# USB_IMU_Board.net
KiCad netlist of a schematic drawn in EAGLE
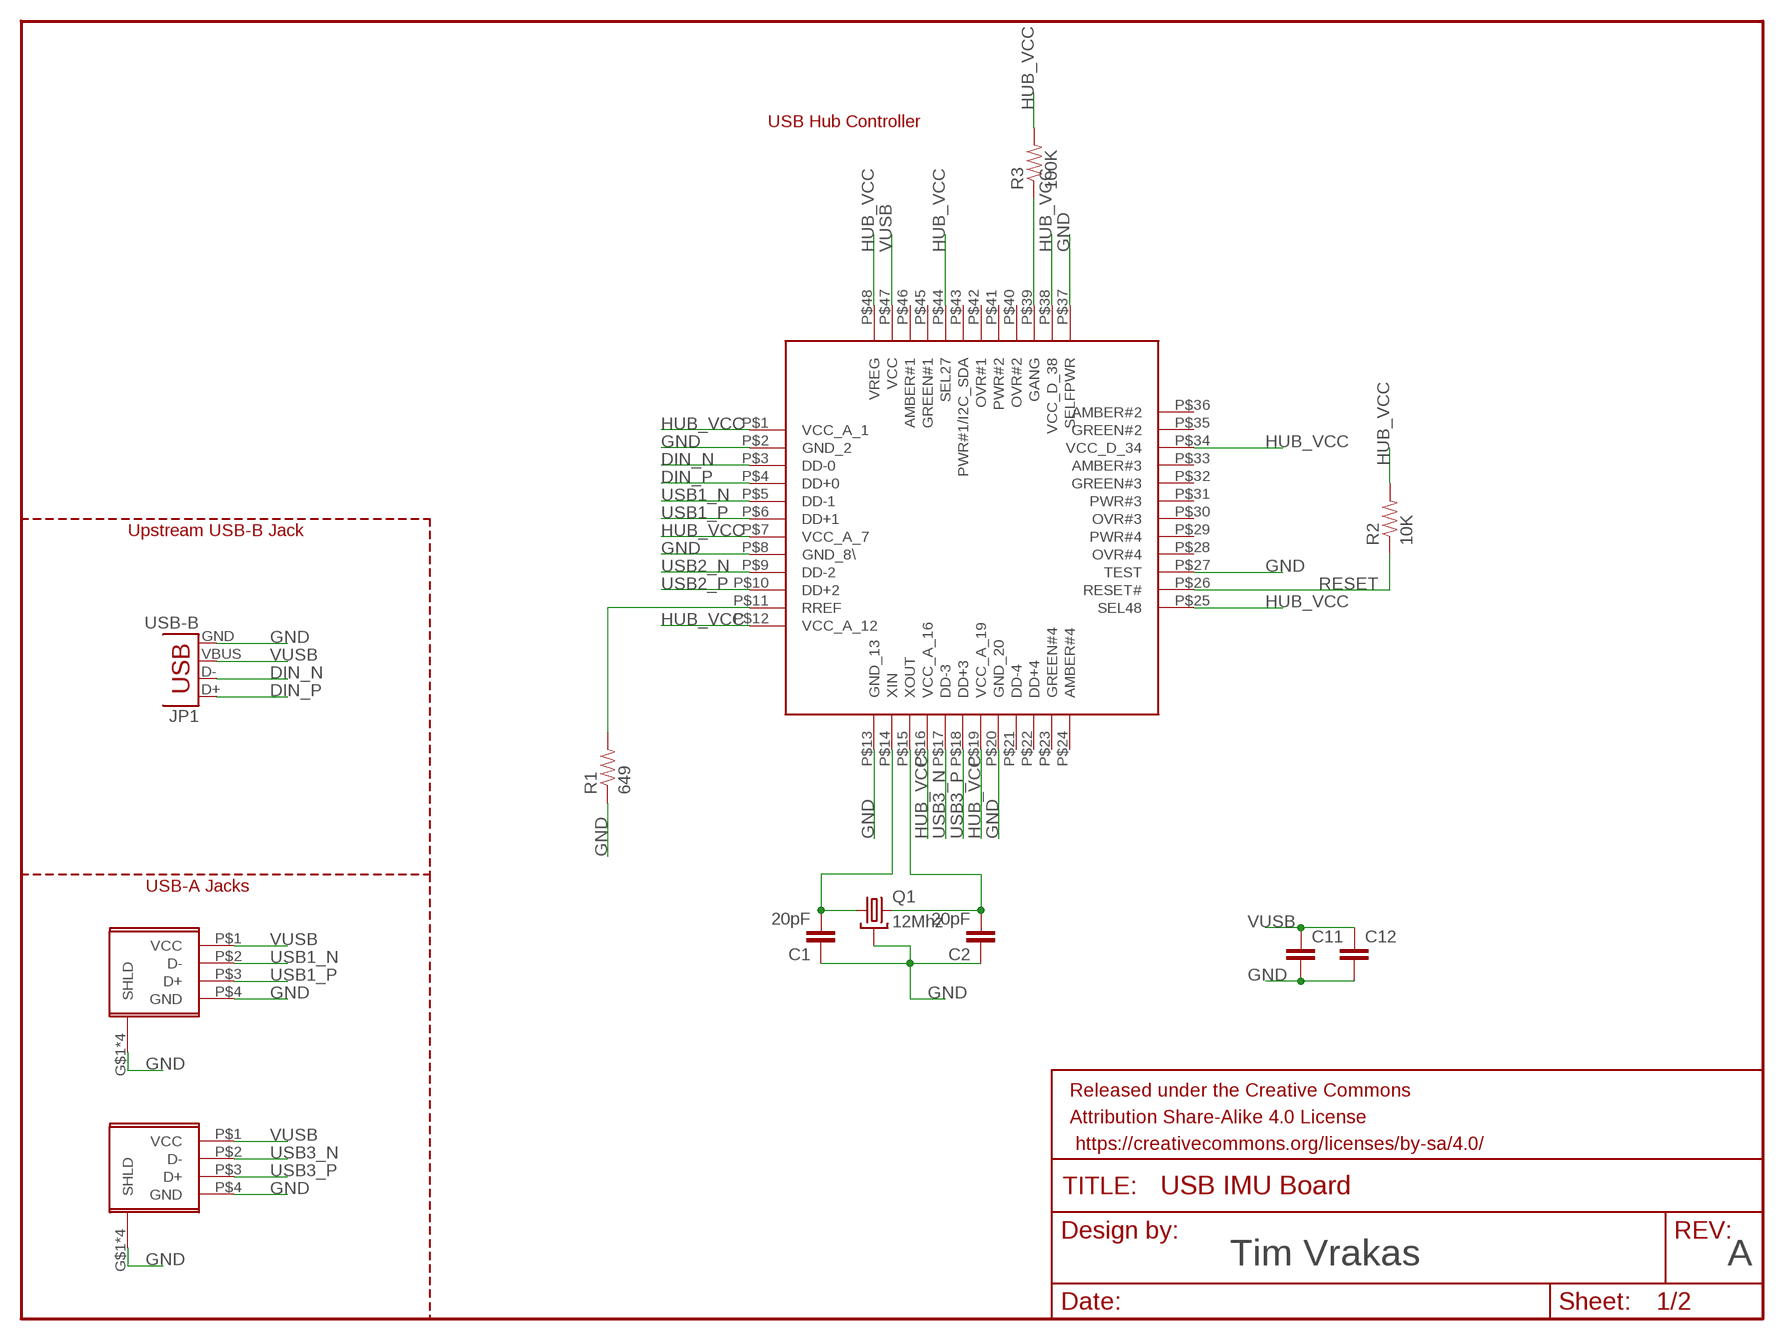
[diagram p0: schematic, sheet 1]
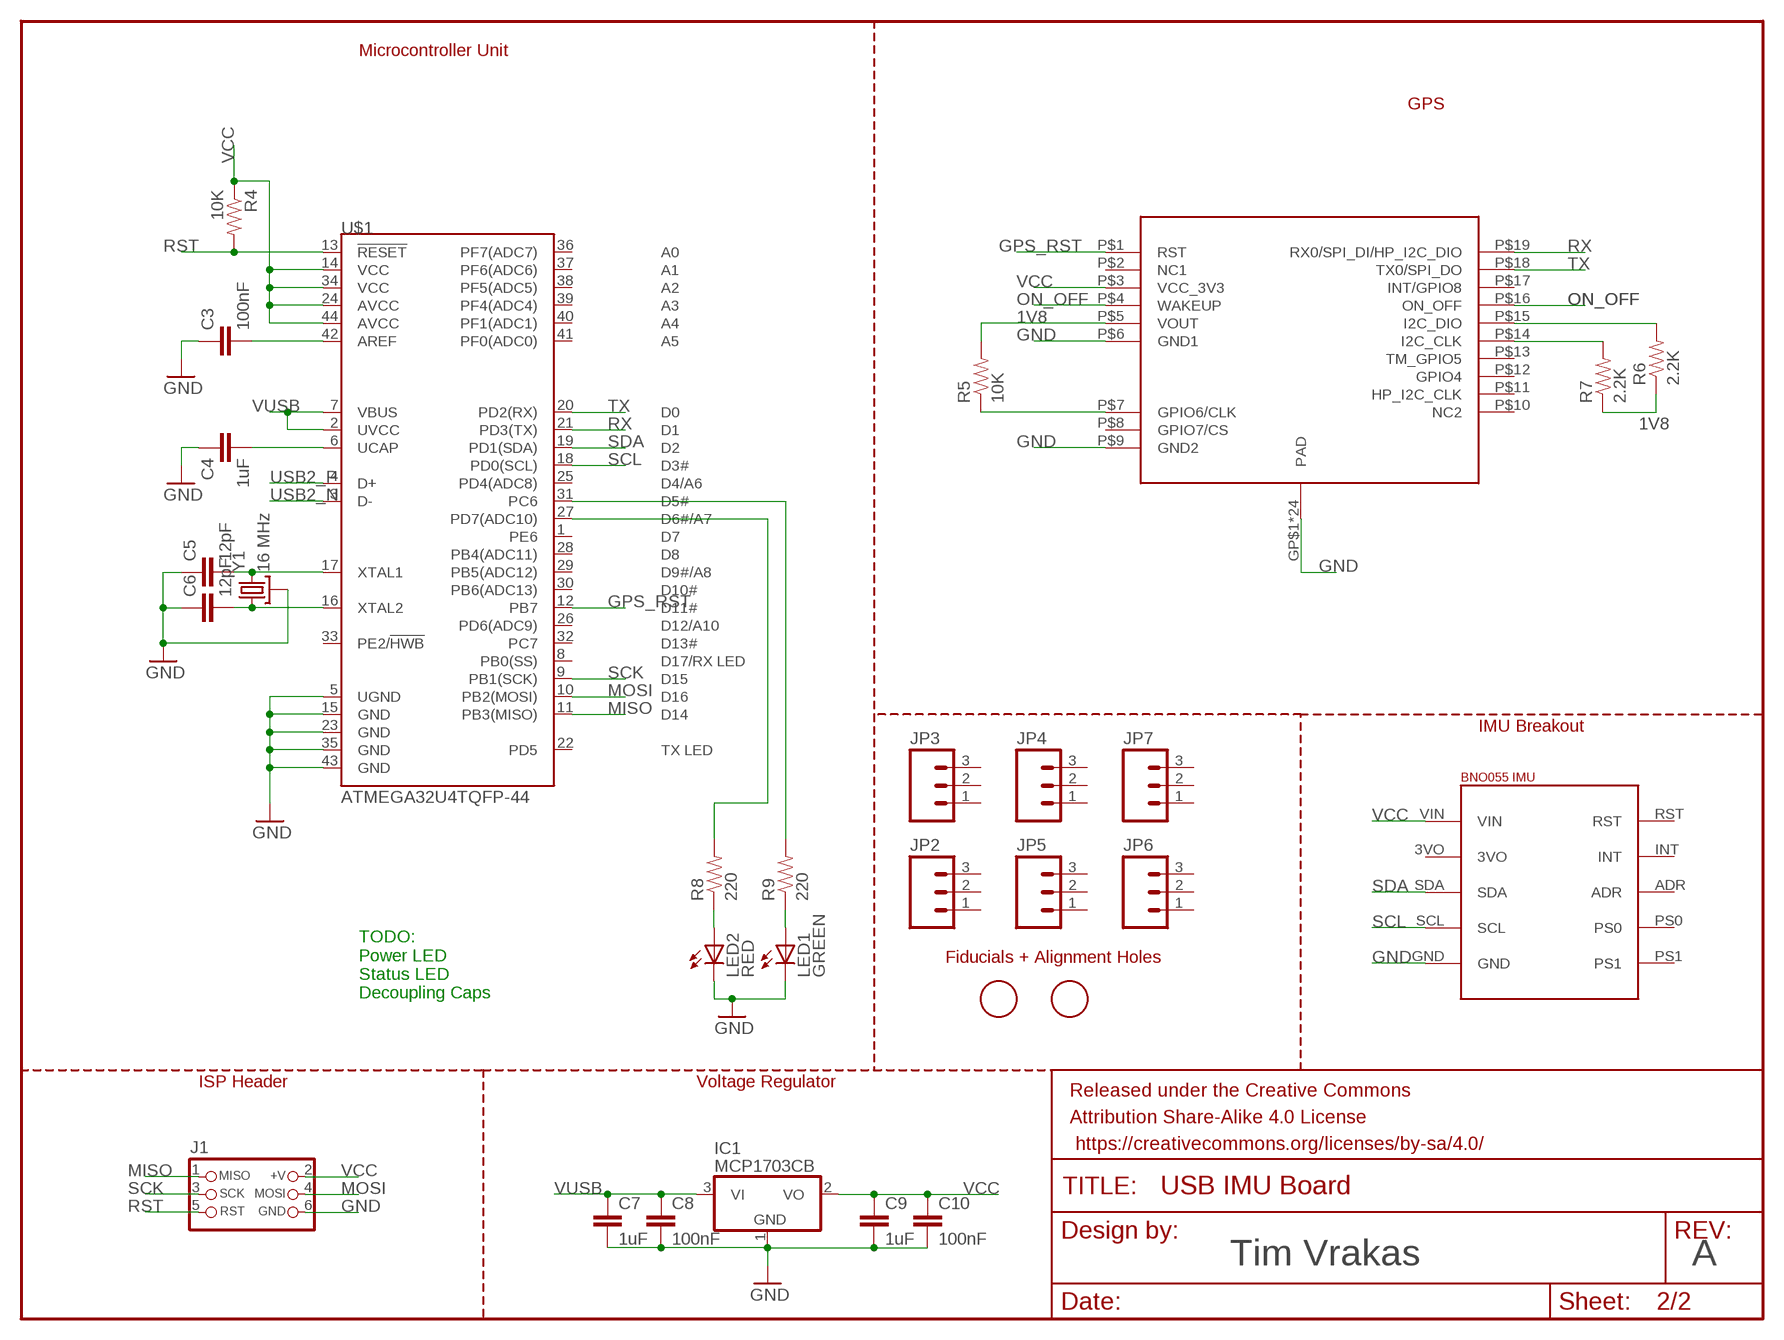
[diagram p1: schematic, sheet 2]

(export (version "E")
  (design (tool "Eeschema 10.0.6"))
  (components
    (comp (ref "C1")
      (value "20pF")
      (footprint "eagle-import:0805")
      (libsource (lib "eagle-import") (part "SparkFun-Passives_CAP0805"))
    )
    (comp (ref "C2")
      (value "20pF")
      (footprint "eagle-import:0805")
      (libsource (lib "eagle-import") (part "SparkFun-Passives_CAP0805"))
    )
    (comp (ref "C11")
      (value "CAP0805")
      (footprint "eagle-import:0805")
      (libsource (lib "eagle-import") (part "CAP0805"))
    )
    (comp (ref "C12")
      (value "CAP0805")
      (footprint "eagle-import:0805")
      (libsource (lib "eagle-import") (part "CAP0805"))
    )
    (comp (ref "FRAME1")
      (value "FRAME-LETTERNO_PACKAGE")
      (footprint "eagle-import:DUMMY")
      (fields
        (field (name "DESIGNER") "Tim Vrakas")
        (field (name "VERSION") "A")
        (field (name "DESIGNER_1") "Tim Vrakas")
        (field (name "VERSION_1") "A")
      )
      (libsource (lib "eagle-import") (part "FRAME-LETTERNO_PACKAGE"))
    )
    (comp (ref "JP1")
      (value "USB-B")
      (footprint "eagle-import:USB-B-PTH")
      (libsource (lib "eagle-import") (part "USBPTH"))
    )
    (comp (ref "Q1")
      (value "12Mhz")
      (footprint "eagle-import:CRYSTAL-SMD-5X3")
      (libsource (lib "eagle-import") (part "CRYSTAL3.2X2.5"))
    )
    (comp (ref "R1")
      (value "649")
      (footprint "eagle-import:0805")
      (libsource (lib "eagle-import") (part "RESISTOR0805-RES"))
    )
    (comp (ref "R2")
      (value "10K")
      (footprint "eagle-import:0805")
      (libsource (lib "eagle-import") (part "RESISTOR0805-RES"))
    )
    (comp (ref "R3")
      (value "100K")
      (footprint "eagle-import:0805")
      (libsource (lib "eagle-import") (part "RESISTOR0805-RES"))
    )
    (comp (ref "U$3")
      (value "CY7C65642")
      (footprint "eagle-import:TQFP-48")
      (libsource (lib "eagle-import") (part "CY7C65642"))
    )
    (comp (ref "U$5")
      (value "USB-SOCKET")
      (footprint "eagle-import:TE-1932854-1-USB")
      (libsource (lib "eagle-import") (part "USB-SOCKET"))
    )
    (comp (ref "U$6")
      (value "USB-SOCKET")
      (footprint "eagle-import:TE-1932854-1-USB")
      (libsource (lib "eagle-import") (part "USB-SOCKET"))
    )
    (comp (ref "C3")
      (value "100nF")
      (footprint "eagle-import:0805")
      (libsource (lib "eagle-import") (part "SparkFun-Passives_CAP0805"))
    )
    (comp (ref "C4")
      (value "1uF")
      (footprint "eagle-import:0805")
      (libsource (lib "eagle-import") (part "SparkFun-Passives_CAP0805"))
    )
    (comp (ref "C5")
      (value "12pF")
      (footprint "eagle-import:0805")
      (libsource (lib "eagle-import") (part "SparkFun-Passives_CAP0805"))
    )
    (comp (ref "C6")
      (value "12pF")
      (footprint "eagle-import:0805")
      (libsource (lib "eagle-import") (part "SparkFun-Passives_CAP0805"))
    )
    (comp (ref "C7")
      (value "1uF")
      (footprint "eagle-import:0805")
      (libsource (lib "eagle-import") (part "SparkFun-Passives_CAP0805"))
    )
    (comp (ref "C8")
      (value "100nF")
      (footprint "eagle-import:0805")
      (libsource (lib "eagle-import") (part "SparkFun-Passives_CAP0805"))
    )
    (comp (ref "C9")
      (value "1uF")
      (footprint "eagle-import:0805")
      (libsource (lib "eagle-import") (part "SparkFun-Passives_CAP0805"))
    )
    (comp (ref "C10")
      (value "100nF")
      (footprint "eagle-import:0805")
      (libsource (lib "eagle-import") (part "SparkFun-Passives_CAP0805"))
    )
    (comp (ref "FRAME2")
      (value "FRAME-LETTERNO_PACKAGE")
      (footprint "eagle-import:DUMMY")
      (fields
        (field (name "DESIGNER") "Nobody")
        (field (name "VERSION") "v01")
        (field (name "DESIGNER_1") "Tim Vrakas")
        (field (name "VERSION_1") "A")
      )
      (libsource (lib "eagle-import") (part "FRAME-LETTERNO_PACKAGE"))
    )
    (comp (ref "IC1")
      (value "MCP1703CB")
      (footprint "eagle-import:SOT23")
      (libsource (lib "eagle-import") (part "MCP1703CB"))
    )
    (comp (ref "J1")
      (value "CON_HEADER_PRG_AVR_ICSP-SMD")
      (footprint "eagle-import:M2X3_SMD")
      (libsource (lib "eagle-import") (part "CON_HEADER_PRG_AVR_ICSP-SMD"))
    )
    (comp (ref "JP2")
      (value "M03PTH")
      (footprint "eagle-import:1X03")
      (libsource (lib "eagle-import") (part "M03PTH"))
    )
    (comp (ref "JP3")
      (value "M03PTH")
      (footprint "eagle-import:1X03")
      (libsource (lib "eagle-import") (part "M03PTH"))
    )
    (comp (ref "JP4")
      (value "M03PTH")
      (footprint "eagle-import:1X03")
      (libsource (lib "eagle-import") (part "M03PTH"))
    )
    (comp (ref "JP5")
      (value "M03PTH")
      (footprint "eagle-import:1X03")
      (libsource (lib "eagle-import") (part "M03PTH"))
    )
    (comp (ref "JP6")
      (value "M03PTH")
      (footprint "eagle-import:1X03")
      (libsource (lib "eagle-import") (part "M03PTH"))
    )
    (comp (ref "JP7")
      (value "M03PTH")
      (footprint "eagle-import:1X03")
      (libsource (lib "eagle-import") (part "M03PTH"))
    )
    (comp (ref "LED1")
      (value "GREEN")
      (footprint "eagle-import:SML0805")
      (libsource (lib "eagle-import") (part "LEDSML0805"))
    )
    (comp (ref "LED2")
      (value "RED")
      (footprint "eagle-import:SML0805")
      (libsource (lib "eagle-import") (part "LEDSML0805"))
    )
    (comp (ref "R4")
      (value "10K")
      (footprint "eagle-import:0805")
      (libsource (lib "eagle-import") (part "RESISTOR0805-RES"))
    )
    (comp (ref "R5")
      (value "10K")
      (footprint "eagle-import:0805")
      (libsource (lib "eagle-import") (part "RESISTOR0805-RES"))
    )
    (comp (ref "R6")
      (value "2.2K")
      (footprint "eagle-import:0805")
      (libsource (lib "eagle-import") (part "RESISTOR0805-RES"))
    )
    (comp (ref "R7")
      (value "2.2K")
      (footprint "eagle-import:0805")
      (libsource (lib "eagle-import") (part "RESISTOR0805-RES"))
    )
    (comp (ref "R8")
      (value "220")
      (footprint "eagle-import:0805")
      (libsource (lib "eagle-import") (part "SparkFun-Resistors_RESISTOR0805-RES"))
    )
    (comp (ref "R9")
      (value "220")
      (footprint "eagle-import:0805")
      (libsource (lib "eagle-import") (part "SparkFun-Resistors_RESISTOR0805-RES"))
    )
    (comp (ref "U$1")
      (value "ATMEGA32U4TQFP-44")
      (footprint "eagle-import:TQFP44")
      (libsource (lib "eagle-import") (part "ATMEGA32U4TQFP-44"))
    )
    (comp (ref "U$2")
      (value "A2235-H")
      (footprint "eagle-import:A2235-H")
      (libsource (lib "eagle-import") (part "A2235-H"))
    )
    (comp (ref "U$4")
      (value "BNO055-IMU")
      (footprint "eagle-import:BNO055-BREAKOUT")
      (libsource (lib "eagle-import") (part "BNO055-IMU"))
    )
    (comp (ref "U$7")
      (value "FIDUCIAL")
      (footprint "eagle-import:FIDUCIAL_1MM")
      (libsource (lib "eagle-import") (part "FIDUCIAL"))
    )
    (comp (ref "U$8")
      (value "FIDUCIAL")
      (footprint "eagle-import:FIDUCIAL_1MM")
      (libsource (lib "eagle-import") (part "FIDUCIAL"))
    )
    (comp (ref "Y1")
      (value "16 MHz")
      (footprint "eagle-import:CRYSTAL-SMD-5X3")
      (libsource (lib "eagle-import") (part "CRYSTAL3.2X2.5"))
    )
  )
  (nets
    (net (code "1") (name "1V8") (class "Default")
      (node (ref "R5") (pin "2") (pinfunction "2_2") (pintype "passive"))
      (node (ref "R6") (pin "1") (pinfunction "1_1") (pintype "passive"))
      (node (ref "R7") (pin "1") (pinfunction "1_1") (pintype "passive"))
      (node (ref "U$2") (pin "P$5") (pinfunction "VOUT_P$5") (pintype "bidirectional"))
    )
    (net (code "2") (name "DIN_N") (class "Default")
      (node (ref "JP1") (pin "D-") (pinfunction "D-_D-") (pintype "bidirectional"))
      (node (ref "U$3") (pin "P$3") (pinfunction "DD-0_P$3") (pintype "bidirectional"))
    )
    (net (code "3") (name "DIN_P") (class "Default")
      (node (ref "JP1") (pin "D+") (pinfunction "D+_D+") (pintype "bidirectional"))
      (node (ref "U$3") (pin "P$4") (pinfunction "DD+0_P$4") (pintype "bidirectional"))
    )
    (net (code "4") (name "GND") (class "Default")
      (node (ref "C1") (pin "1") (pinfunction "1_1") (pintype "passive"))
      (node (ref "C10") (pin "2") (pinfunction "2_2") (pintype "passive"))
      (node (ref "C11") (pin "2") (pinfunction "2_2") (pintype "passive"))
      (node (ref "C12") (pin "2") (pinfunction "2_2") (pintype "passive"))
      (node (ref "C2") (pin "1") (pinfunction "1_1") (pintype "passive"))
      (node (ref "C3") (pin "1") (pinfunction "1_1") (pintype "passive"))
      (node (ref "C4") (pin "1") (pinfunction "1_1") (pintype "passive"))
      (node (ref "C5") (pin "1") (pinfunction "1_1") (pintype "passive"))
      (node (ref "C6") (pin "1") (pinfunction "1_1") (pintype "passive"))
      (node (ref "C7") (pin "2") (pinfunction "2_2") (pintype "passive"))
      (node (ref "C8") (pin "2") (pinfunction "2_2") (pintype "passive"))
      (node (ref "C9") (pin "2") (pinfunction "2_2") (pintype "passive"))
      (node (ref "IC1") (pin "1") (pinfunction "GND_1") (pintype "passive"))
      (node (ref "J1") (pin "6") (pinfunction "GND_6") (pintype "passive"))
      (node (ref "JP1") (pin "GND") (pinfunction "GND_GND") (pintype "bidirectional"))
      (node (ref "LED1") (pin "C") (pinfunction "C_C") (pintype "passive"))
      (node (ref "LED2") (pin "C") (pinfunction "C_C") (pintype "passive"))
      (node (ref "Q1") (pin "2") (pinfunction "GND_2") (pintype "power_in"))
      (node (ref "Q1") (pin "4") (pinfunction "GND_4") (pintype "power_in"))
      (node (ref "R1") (pin "1") (pinfunction "1_1") (pintype "passive"))
      (node (ref "U$1") (pin "15") (pinfunction "GND_15") (pintype "bidirectional"))
      (node (ref "U$1") (pin "23") (pinfunction "GND_23") (pintype "bidirectional"))
      (node (ref "U$1") (pin "35") (pinfunction "GND_35") (pintype "bidirectional"))
      (node (ref "U$1") (pin "43") (pinfunction "GND_43") (pintype "bidirectional"))
      (node (ref "U$1") (pin "5") (pinfunction "UGND_5") (pintype "bidirectional"))
      (node (ref "U$2") (pin "GP$1") (pinfunction "PAD_GP$1") (pintype "bidirectional"))
      (node (ref "U$2") (pin "GP$10") (pinfunction "PAD_GP$10") (pintype "bidirectional"))
      (node (ref "U$2") (pin "GP$11") (pinfunction "PAD_GP$11") (pintype "bidirectional"))
      (node (ref "U$2") (pin "GP$12") (pinfunction "PAD_GP$12") (pintype "bidirectional"))
      (node (ref "U$2") (pin "GP$13") (pinfunction "PAD_GP$13") (pintype "bidirectional"))
      (node (ref "U$2") (pin "GP$14") (pinfunction "PAD_GP$14") (pintype "bidirectional"))
      (node (ref "U$2") (pin "GP$15") (pinfunction "PAD_GP$15") (pintype "bidirectional"))
      (node (ref "U$2") (pin "GP$16") (pinfunction "PAD_GP$16") (pintype "bidirectional"))
      (node (ref "U$2") (pin "GP$17") (pinfunction "PAD_GP$17") (pintype "bidirectional"))
      (node (ref "U$2") (pin "GP$18") (pinfunction "PAD_GP$18") (pintype "bidirectional"))
      (node (ref "U$2") (pin "GP$19") (pinfunction "PAD_GP$19") (pintype "bidirectional"))
      (node (ref "U$2") (pin "GP$2") (pinfunction "PAD_GP$2") (pintype "bidirectional"))
      (node (ref "U$2") (pin "GP$20") (pinfunction "PAD_GP$20") (pintype "bidirectional"))
      (node (ref "U$2") (pin "GP$21") (pinfunction "PAD_GP$21") (pintype "bidirectional"))
      (node (ref "U$2") (pin "GP$22") (pinfunction "PAD_GP$22") (pintype "bidirectional"))
      (node (ref "U$2") (pin "GP$23") (pinfunction "PAD_GP$23") (pintype "bidirectional"))
      (node (ref "U$2") (pin "GP$24") (pinfunction "PAD_GP$24") (pintype "bidirectional"))
      (node (ref "U$2") (pin "GP$3") (pinfunction "PAD_GP$3") (pintype "bidirectional"))
      (node (ref "U$2") (pin "GP$4") (pinfunction "PAD_GP$4") (pintype "bidirectional"))
      (node (ref "U$2") (pin "GP$5") (pinfunction "PAD_GP$5") (pintype "bidirectional"))
      (node (ref "U$2") (pin "GP$6") (pinfunction "PAD_GP$6") (pintype "bidirectional"))
      (node (ref "U$2") (pin "GP$7") (pinfunction "PAD_GP$7") (pintype "bidirectional"))
      (node (ref "U$2") (pin "GP$8") (pinfunction "PAD_GP$8") (pintype "bidirectional"))
      (node (ref "U$2") (pin "GP$9") (pinfunction "PAD_GP$9") (pintype "bidirectional"))
      (node (ref "U$2") (pin "P$6") (pinfunction "GND1_P$6") (pintype "bidirectional"))
      (node (ref "U$2") (pin "P$9") (pinfunction "GND2_P$9") (pintype "bidirectional"))
      (node (ref "U$3") (pin "P$13") (pinfunction "GND_13_P$13") (pintype "bidirectional"))
      (node (ref "U$3") (pin "P$2") (pinfunction "GND_2_P$2") (pintype "bidirectional"))
      (node (ref "U$3") (pin "P$20") (pinfunction "GND_20_P$20") (pintype "bidirectional"))
      (node (ref "U$3") (pin "P$27") (pinfunction "TEST_P$27") (pintype "bidirectional"))
      (node (ref "U$3") (pin "P$37") (pinfunction "SELFPWR_P$37") (pintype "bidirectional"))
      (node (ref "U$3") (pin "P$8") (pinfunction "GND_8\\_P$8") (pintype "bidirectional"))
      (node (ref "U$4") (pin "GND") (pinfunction "GND_GND") (pintype "bidirectional"))
      (node (ref "U$5") (pin "G$1") (pinfunction "SHLD_G$1") (pintype "bidirectional"))
      (node (ref "U$5") (pin "G$2") (pinfunction "SHLD_G$2") (pintype "bidirectional"))
      (node (ref "U$5") (pin "G$3") (pinfunction "SHLD_G$3") (pintype "bidirectional"))
      (node (ref "U$5") (pin "G$4") (pinfunction "SHLD_G$4") (pintype "bidirectional"))
      (node (ref "U$5") (pin "P$4") (pinfunction "GND_P$4") (pintype "bidirectional"))
      (node (ref "U$6") (pin "G$1") (pinfunction "SHLD_G$1") (pintype "bidirectional"))
      (node (ref "U$6") (pin "G$2") (pinfunction "SHLD_G$2") (pintype "bidirectional"))
      (node (ref "U$6") (pin "G$3") (pinfunction "SHLD_G$3") (pintype "bidirectional"))
      (node (ref "U$6") (pin "G$4") (pinfunction "SHLD_G$4") (pintype "bidirectional"))
      (node (ref "U$6") (pin "P$4") (pinfunction "GND_P$4") (pintype "bidirectional"))
      (node (ref "Y1") (pin "2") (pinfunction "GND_2") (pintype "power_in"))
      (node (ref "Y1") (pin "4") (pinfunction "GND_4") (pintype "power_in"))
    )
    (net (code "5") (name "GPS_RST") (class "Default")
      (node (ref "U$1") (pin "12") (pinfunction "PB7_12") (pintype "bidirectional"))
      (node (ref "U$2") (pin "P$1") (pinfunction "RST_P$1") (pintype "bidirectional"))
    )
    (net (code "6") (name "HUB_VCC") (class "Default")
      (node (ref "R2") (pin "2") (pinfunction "2_2") (pintype "passive"))
      (node (ref "R3") (pin "2") (pinfunction "2_2") (pintype "passive"))
      (node (ref "U$3") (pin "P$1") (pinfunction "VCC_A_1_P$1") (pintype "bidirectional"))
      (node (ref "U$3") (pin "P$12") (pinfunction "VCC_A_12_P$12") (pintype "bidirectional"))
      (node (ref "U$3") (pin "P$16") (pinfunction "VCC_A_16_P$16") (pintype "bidirectional"))
      (node (ref "U$3") (pin "P$19") (pinfunction "VCC_A_19_P$19") (pintype "bidirectional"))
      (node (ref "U$3") (pin "P$25") (pinfunction "SEL48_P$25") (pintype "bidirectional"))
      (node (ref "U$3") (pin "P$34") (pinfunction "VCC_D_34_P$34") (pintype "bidirectional"))
      (node (ref "U$3") (pin "P$38") (pinfunction "VCC_D_38_P$38") (pintype "bidirectional"))
      (node (ref "U$3") (pin "P$44") (pinfunction "SEL27_P$44") (pintype "bidirectional"))
      (node (ref "U$3") (pin "P$48") (pinfunction "VREG_P$48") (pintype "bidirectional"))
      (node (ref "U$3") (pin "P$7") (pinfunction "VCC_A_7_P$7") (pintype "bidirectional"))
    )
    (net (code "7") (name "MISO") (class "Default")
      (node (ref "J1") (pin "1") (pinfunction "MISO_1") (pintype "passive"))
      (node (ref "U$1") (pin "11") (pinfunction "PB3(MISO)_11") (pintype "bidirectional"))
    )
    (net (code "8") (name "MOSI") (class "Default")
      (node (ref "J1") (pin "4") (pinfunction "MOSI_4") (pintype "passive"))
      (node (ref "U$1") (pin "10") (pinfunction "PB2(MOSI)_10") (pintype "bidirectional"))
    )
    (net (code "9") (name "Net-(LED1-PadA)") (class "Default")
      (node (ref "LED1") (pin "A") (pinfunction "A_A") (pintype "passive"))
      (node (ref "R9") (pin "1") (pinfunction "1_1") (pintype "passive"))
    )
    (net (code "10") (name "Net-(LED2-PadA)") (class "Default")
      (node (ref "LED2") (pin "A") (pinfunction "A_A") (pintype "passive"))
      (node (ref "R8") (pin "1") (pinfunction "1_1") (pintype "passive"))
    )
    (net (code "11") (name "Net-(Q1-2)") (class "Default")
      (node (ref "C2") (pin "2") (pinfunction "2_2") (pintype "passive"))
      (node (ref "Q1") (pin "3") (pinfunction "2_3") (pintype "passive"))
      (node (ref "U$3") (pin "P$15") (pinfunction "XOUT_P$15") (pintype "bidirectional"))
    )
    (net (code "12") (name "Net-(U$1-AREF)") (class "Default")
      (node (ref "C3") (pin "2") (pinfunction "2_2") (pintype "passive"))
      (node (ref "U$1") (pin "42") (pinfunction "AREF_42") (pintype "bidirectional"))
    )
    (net (code "13") (name "Net-(U$1-PC6)") (class "Default")
      (node (ref "R9") (pin "2") (pinfunction "2_2") (pintype "passive"))
      (node (ref "U$1") (pin "31") (pinfunction "PC6_31") (pintype "bidirectional"))
    )
    (net (code "14") (name "Net-(U$1-PD7(ADC10))") (class "Default")
      (node (ref "R8") (pin "2") (pinfunction "2_2") (pintype "passive"))
      (node (ref "U$1") (pin "27") (pinfunction "PD7(ADC10)_27") (pintype "bidirectional"))
    )
    (net (code "15") (name "Net-(U$1-UCAP)") (class "Default")
      (node (ref "C4") (pin "2") (pinfunction "2_2") (pintype "passive"))
      (node (ref "U$1") (pin "6") (pinfunction "UCAP_6") (pintype "bidirectional"))
    )
    (net (code "16") (name "Net-(U$1-XTAL1)") (class "Default")
      (node (ref "C5") (pin "2") (pinfunction "2_2") (pintype "passive"))
      (node (ref "U$1") (pin "17") (pinfunction "XTAL1_17") (pintype "bidirectional"))
      (node (ref "Y1") (pin "3") (pinfunction "2_3") (pintype "passive"))
    )
    (net (code "17") (name "Net-(U$1-XTAL2)") (class "Default")
      (node (ref "C6") (pin "2") (pinfunction "2_2") (pintype "passive"))
      (node (ref "U$1") (pin "16") (pinfunction "XTAL2_16") (pintype "bidirectional"))
      (node (ref "Y1") (pin "1") (pinfunction "1_1") (pintype "passive"))
    )
    (net (code "18") (name "Net-(U$2-GPIO6{slash}CLK)") (class "Default")
      (node (ref "R5") (pin "1") (pinfunction "1_1") (pintype "passive"))
      (node (ref "U$2") (pin "P$7") (pinfunction "GPIO6/CLK_P$7") (pintype "bidirectional"))
    )
    (net (code "19") (name "Net-(U$2-I2C_CLK)") (class "Default")
      (node (ref "R7") (pin "2") (pinfunction "2_2") (pintype "passive"))
      (node (ref "U$2") (pin "P$14") (pinfunction "I2C_CLK_P$14") (pintype "bidirectional"))
    )
    (net (code "20") (name "Net-(U$2-I2C_DIO)") (class "Default")
      (node (ref "R6") (pin "2") (pinfunction "2_2") (pintype "passive"))
      (node (ref "U$2") (pin "P$15") (pinfunction "I2C_DIO_P$15") (pintype "bidirectional"))
    )
    (net (code "21") (name "Net-(U$3-GANG)") (class "Default")
      (node (ref "R3") (pin "1") (pinfunction "1_1") (pintype "passive"))
      (node (ref "U$3") (pin "P$39") (pinfunction "GANG_P$39") (pintype "bidirectional"))
    )
    (net (code "22") (name "Net-(U$3-RREF)") (class "Default")
      (node (ref "R1") (pin "2") (pinfunction "2_2") (pintype "passive"))
      (node (ref "U$3") (pin "P$11") (pinfunction "RREF_P$11") (pintype "bidirectional"))
    )
    (net (code "23") (name "Net-(U$3-XIN)") (class "Default")
      (node (ref "C1") (pin "2") (pinfunction "2_2") (pintype "passive"))
      (node (ref "Q1") (pin "1") (pinfunction "1_1") (pintype "passive"))
      (node (ref "U$3") (pin "P$14") (pinfunction "XIN_P$14") (pintype "bidirectional"))
    )
    (net (code "24") (name "ON_OFF") (class "Default")
      (node (ref "U$2") (pin "P$16") (pinfunction "ON_OFF_P$16") (pintype "bidirectional"))
      (node (ref "U$2") (pin "P$4") (pinfunction "WAKEUP_P$4") (pintype "bidirectional"))
    )
    (net (code "25") (name "RESET") (class "Default")
      (node (ref "R2") (pin "1") (pinfunction "1_1") (pintype "passive"))
      (node (ref "U$3") (pin "P$26") (pinfunction "RESET#_P$26") (pintype "bidirectional"))
    )
    (net (code "26") (name "RST") (class "Default")
      (node (ref "J1") (pin "5") (pinfunction "RST_5") (pintype "passive"))
      (node (ref "R4") (pin "2") (pinfunction "2_2") (pintype "passive"))
      (node (ref "U$1") (pin "13") (pinfunction "~{RESET}_13") (pintype "bidirectional"))
    )
    (net (code "27") (name "RX") (class "Default")
      (node (ref "U$1") (pin "21") (pinfunction "PD3(TX)_21") (pintype "bidirectional"))
      (node (ref "U$2") (pin "P$19") (pinfunction "RX0/SPI_DI/HP_I2C_DIO_P$19") (pintype "bidirectional"))
    )
    (net (code "28") (name "SCK") (class "Default")
      (node (ref "J1") (pin "3") (pinfunction "SCK_3") (pintype "passive"))
      (node (ref "U$1") (pin "9") (pinfunction "PB1(SCK)_9") (pintype "bidirectional"))
    )
    (net (code "29") (name "SCL") (class "Default")
      (node (ref "U$1") (pin "18") (pinfunction "PD0(SCL)_18") (pintype "bidirectional"))
      (node (ref "U$4") (pin "SCL") (pinfunction "SCL_SCL") (pintype "bidirectional"))
    )
    (net (code "30") (name "SDA") (class "Default")
      (node (ref "U$1") (pin "19") (pinfunction "PD1(SDA)_19") (pintype "bidirectional"))
      (node (ref "U$4") (pin "SDA") (pinfunction "SDA_SDA") (pintype "bidirectional"))
    )
    (net (code "31") (name "TX") (class "Default")
      (node (ref "U$1") (pin "20") (pinfunction "PD2(RX)_20") (pintype "bidirectional"))
      (node (ref "U$2") (pin "P$18") (pinfunction "TX0/SPI_DO_P$18") (pintype "bidirectional"))
    )
    (net (code "32") (name "USB1_N") (class "Default")
      (node (ref "U$3") (pin "P$5") (pinfunction "DD-1_P$5") (pintype "bidirectional"))
      (node (ref "U$5") (pin "P$2") (pinfunction "D-_P$2") (pintype "bidirectional"))
    )
    (net (code "33") (name "USB1_P") (class "Default")
      (node (ref "U$3") (pin "P$6") (pinfunction "DD+1_P$6") (pintype "bidirectional"))
      (node (ref "U$5") (pin "P$3") (pinfunction "D+_P$3") (pintype "bidirectional"))
    )
    (net (code "34") (name "USB2_N") (class "Default")
      (node (ref "U$1") (pin "3") (pinfunction "D-_3") (pintype "bidirectional"))
      (node (ref "U$3") (pin "P$9") (pinfunction "DD-2_P$9") (pintype "bidirectional"))
    )
    (net (code "35") (name "USB2_P") (class "Default")
      (node (ref "U$1") (pin "4") (pinfunction "D+_4") (pintype "bidirectional"))
      (node (ref "U$3") (pin "P$10") (pinfunction "DD+2_P$10") (pintype "bidirectional"))
    )
    (net (code "36") (name "USB3_N") (class "Default")
      (node (ref "U$3") (pin "P$17") (pinfunction "DD-3_P$17") (pintype "bidirectional"))
      (node (ref "U$6") (pin "P$2") (pinfunction "D-_P$2") (pintype "bidirectional"))
    )
    (net (code "37") (name "USB3_P") (class "Default")
      (node (ref "U$3") (pin "P$18") (pinfunction "DD+3_P$18") (pintype "bidirectional"))
      (node (ref "U$6") (pin "P$3") (pinfunction "D+_P$3") (pintype "bidirectional"))
    )
    (net (code "38") (name "VCC") (class "Default")
      (node (ref "C10") (pin "1") (pinfunction "1_1") (pintype "passive"))
      (node (ref "C9") (pin "1") (pinfunction "1_1") (pintype "passive"))
      (node (ref "IC1") (pin "2") (pinfunction "VO_2") (pintype "passive"))
      (node (ref "J1") (pin "2") (pinfunction "+V_2") (pintype "passive"))
      (node (ref "R4") (pin "1") (pinfunction "1_1") (pintype "passive"))
      (node (ref "U$1") (pin "14") (pinfunction "VCC_14") (pintype "bidirectional"))
      (node (ref "U$1") (pin "24") (pinfunction "AVCC_24") (pintype "bidirectional"))
      (node (ref "U$1") (pin "34") (pinfunction "VCC_34") (pintype "bidirectional"))
      (node (ref "U$1") (pin "44") (pinfunction "AVCC_44") (pintype "bidirectional"))
      (node (ref "U$2") (pin "P$3") (pinfunction "VCC_3V3_P$3") (pintype "bidirectional"))
      (node (ref "U$4") (pin "VIN") (pinfunction "VIN_VIN") (pintype "bidirectional"))
    )
    (net (code "39") (name "VUSB") (class "Default")
      (node (ref "C11") (pin "1") (pinfunction "1_1") (pintype "passive"))
      (node (ref "C12") (pin "1") (pinfunction "1_1") (pintype "passive"))
      (node (ref "C7") (pin "1") (pinfunction "1_1") (pintype "passive"))
      (node (ref "C8") (pin "1") (pinfunction "1_1") (pintype "passive"))
      (node (ref "IC1") (pin "3") (pinfunction "VI_3") (pintype "input"))
      (node (ref "JP1") (pin "VBUS") (pinfunction "VBUS_VBUS") (pintype "bidirectional"))
      (node (ref "U$1") (pin "2") (pinfunction "UVCC_2") (pintype "bidirectional"))
      (node (ref "U$1") (pin "7") (pinfunction "VBUS_7") (pintype "bidirectional"))
      (node (ref "U$3") (pin "P$47") (pinfunction "VCC_P$47") (pintype "bidirectional"))
      (node (ref "U$5") (pin "P$1") (pinfunction "VCC_P$1") (pintype "bidirectional"))
      (node (ref "U$6") (pin "P$1") (pinfunction "VCC_P$1") (pintype "bidirectional"))
    )
    (net (code "40") (name "unconnected-(JP2-Pad1)") (class "Default")
      (node (ref "JP2") (pin "1") (pinfunction "1_1") (pintype "passive"))
    )
    (net (code "41") (name "unconnected-(JP2-Pad2)") (class "Default")
      (node (ref "JP2") (pin "2") (pinfunction "2_2") (pintype "passive"))
    )
    (net (code "42") (name "unconnected-(JP2-Pad3)") (class "Default")
      (node (ref "JP2") (pin "3") (pinfunction "3_3") (pintype "passive"))
    )
    (net (code "43") (name "unconnected-(JP3-Pad1)") (class "Default")
      (node (ref "JP3") (pin "1") (pinfunction "1_1") (pintype "passive"))
    )
    (net (code "44") (name "unconnected-(JP3-Pad2)") (class "Default")
      (node (ref "JP3") (pin "2") (pinfunction "2_2") (pintype "passive"))
    )
    (net (code "45") (name "unconnected-(JP3-Pad3)") (class "Default")
      (node (ref "JP3") (pin "3") (pinfunction "3_3") (pintype "passive"))
    )
    (net (code "46") (name "unconnected-(JP4-Pad1)") (class "Default")
      (node (ref "JP4") (pin "1") (pinfunction "1_1") (pintype "passive"))
    )
    (net (code "47") (name "unconnected-(JP4-Pad2)") (class "Default")
      (node (ref "JP4") (pin "2") (pinfunction "2_2") (pintype "passive"))
    )
    (net (code "48") (name "unconnected-(JP4-Pad3)") (class "Default")
      (node (ref "JP4") (pin "3") (pinfunction "3_3") (pintype "passive"))
    )
    (net (code "49") (name "unconnected-(JP5-Pad1)") (class "Default")
      (node (ref "JP5") (pin "1") (pinfunction "1_1") (pintype "passive"))
    )
    (net (code "50") (name "unconnected-(JP5-Pad2)") (class "Default")
      (node (ref "JP5") (pin "2") (pinfunction "2_2") (pintype "passive"))
    )
    (net (code "51") (name "unconnected-(JP5-Pad3)") (class "Default")
      (node (ref "JP5") (pin "3") (pinfunction "3_3") (pintype "passive"))
    )
    (net (code "52") (name "unconnected-(JP6-Pad1)") (class "Default")
      (node (ref "JP6") (pin "1") (pinfunction "1_1") (pintype "passive"))
    )
    (net (code "53") (name "unconnected-(JP6-Pad2)") (class "Default")
      (node (ref "JP6") (pin "2") (pinfunction "2_2") (pintype "passive"))
    )
    (net (code "54") (name "unconnected-(JP6-Pad3)") (class "Default")
      (node (ref "JP6") (pin "3") (pinfunction "3_3") (pintype "passive"))
    )
    (net (code "55") (name "unconnected-(JP7-Pad1)") (class "Default")
      (node (ref "JP7") (pin "1") (pinfunction "1_1") (pintype "passive"))
    )
    (net (code "56") (name "unconnected-(JP7-Pad2)") (class "Default")
      (node (ref "JP7") (pin "2") (pinfunction "2_2") (pintype "passive"))
    )
    (net (code "57") (name "unconnected-(JP7-Pad3)") (class "Default")
      (node (ref "JP7") (pin "3") (pinfunction "3_3") (pintype "passive"))
    )
    (net (code "58") (name "unconnected-(U$1-PB0(SS)-Pad8)") (class "Default")
      (node (ref "U$1") (pin "8") (pinfunction "PB0(SS)_8") (pintype "bidirectional"))
    )
    (net (code "59") (name "unconnected-(U$1-PB4(ADC11)-Pad28)") (class "Default")
      (node (ref "U$1") (pin "28") (pinfunction "PB4(ADC11)_28") (pintype "bidirectional"))
    )
    (net (code "60") (name "unconnected-(U$1-PB5(ADC12)-Pad29)") (class "Default")
      (node (ref "U$1") (pin "29") (pinfunction "PB5(ADC12)_29") (pintype "bidirectional"))
    )
    (net (code "61") (name "unconnected-(U$1-PB6(ADC13)-Pad30)") (class "Default")
      (node (ref "U$1") (pin "30") (pinfunction "PB6(ADC13)_30") (pintype "bidirectional"))
    )
    (net (code "62") (name "unconnected-(U$1-PC7-Pad32)") (class "Default")
      (node (ref "U$1") (pin "32") (pinfunction "PC7_32") (pintype "bidirectional"))
    )
    (net (code "63") (name "unconnected-(U$1-PD4(ADC8)-Pad25)") (class "Default")
      (node (ref "U$1") (pin "25") (pinfunction "PD4(ADC8)_25") (pintype "bidirectional"))
    )
    (net (code "64") (name "unconnected-(U$1-PD5-Pad22)") (class "Default")
      (node (ref "U$1") (pin "22") (pinfunction "PD5_22") (pintype "bidirectional"))
    )
    (net (code "65") (name "unconnected-(U$1-PD6(ADC9)-Pad26)") (class "Default")
      (node (ref "U$1") (pin "26") (pinfunction "PD6(ADC9)_26") (pintype "bidirectional"))
    )
    (net (code "66") (name "unconnected-(U$1-PE2{slash}~{HWB}-Pad33)") (class "Default")
      (node (ref "U$1") (pin "33") (pinfunction "PE2/~{HWB}_33") (pintype "bidirectional"))
    )
    (net (code "67") (name "unconnected-(U$1-PE6-Pad1)") (class "Default")
      (node (ref "U$1") (pin "1") (pinfunction "PE6_1") (pintype "bidirectional"))
    )
    (net (code "68") (name "unconnected-(U$1-PF0(ADC0)-Pad41)") (class "Default")
      (node (ref "U$1") (pin "41") (pinfunction "PF0(ADC0)_41") (pintype "bidirectional"))
    )
    (net (code "69") (name "unconnected-(U$1-PF1(ADC1)-Pad40)") (class "Default")
      (node (ref "U$1") (pin "40") (pinfunction "PF1(ADC1)_40") (pintype "bidirectional"))
    )
    (net (code "70") (name "unconnected-(U$1-PF4(ADC4)-Pad39)") (class "Default")
      (node (ref "U$1") (pin "39") (pinfunction "PF4(ADC4)_39") (pintype "bidirectional"))
    )
    (net (code "71") (name "unconnected-(U$1-PF5(ADC5)-Pad38)") (class "Default")
      (node (ref "U$1") (pin "38") (pinfunction "PF5(ADC5)_38") (pintype "bidirectional"))
    )
    (net (code "72") (name "unconnected-(U$1-PF6(ADC6)-Pad37)") (class "Default")
      (node (ref "U$1") (pin "37") (pinfunction "PF6(ADC6)_37") (pintype "bidirectional"))
    )
    (net (code "73") (name "unconnected-(U$1-PF7(ADC7)-Pad36)") (class "Default")
      (node (ref "U$1") (pin "36") (pinfunction "PF7(ADC7)_36") (pintype "bidirectional"))
    )
    (net (code "74") (name "unconnected-(U$2-GPIO4-PadP$12)") (class "Default")
      (node (ref "U$2") (pin "P$12") (pinfunction "GPIO4_P$12") (pintype "bidirectional"))
    )
    (net (code "75") (name "unconnected-(U$2-GPIO7{slash}CS-PadP$8)") (class "Default")
      (node (ref "U$2") (pin "P$8") (pinfunction "GPIO7/CS_P$8") (pintype "bidirectional"))
    )
    (net (code "76") (name "unconnected-(U$2-HP_I2C_CLK-PadP$11)") (class "Default")
      (node (ref "U$2") (pin "P$11") (pinfunction "HP_I2C_CLK_P$11") (pintype "bidirectional"))
    )
    (net (code "77") (name "unconnected-(U$2-INT{slash}GPIO8-PadP$17)") (class "Default")
      (node (ref "U$2") (pin "P$17") (pinfunction "INT/GPIO8_P$17") (pintype "bidirectional"))
    )
    (net (code "78") (name "unconnected-(U$2-NC1-PadP$2)") (class "Default")
      (node (ref "U$2") (pin "P$2") (pinfunction "NC1_P$2") (pintype "bidirectional"))
    )
    (net (code "79") (name "unconnected-(U$2-NC2-PadP$10)") (class "Default")
      (node (ref "U$2") (pin "P$10") (pinfunction "NC2_P$10") (pintype "bidirectional"))
    )
    (net (code "80") (name "unconnected-(U$2-TM_GPIO5-PadP$13)") (class "Default")
      (node (ref "U$2") (pin "P$13") (pinfunction "TM_GPIO5_P$13") (pintype "bidirectional"))
    )
    (net (code "81") (name "unconnected-(U$3-AMBER#1-PadP$46)") (class "Default")
      (node (ref "U$3") (pin "P$46") (pinfunction "AMBER#1_P$46") (pintype "bidirectional"))
    )
    (net (code "82") (name "unconnected-(U$3-AMBER#2-PadP$36)") (class "Default")
      (node (ref "U$3") (pin "P$36") (pinfunction "AMBER#2_P$36") (pintype "bidirectional"))
    )
    (net (code "83") (name "unconnected-(U$3-AMBER#3-PadP$33)") (class "Default")
      (node (ref "U$3") (pin "P$33") (pinfunction "AMBER#3_P$33") (pintype "bidirectional"))
    )
    (net (code "84") (name "unconnected-(U$3-AMBER#4-PadP$24)") (class "Default")
      (node (ref "U$3") (pin "P$24") (pinfunction "AMBER#4_P$24") (pintype "bidirectional"))
    )
    (net (code "85") (name "unconnected-(U$3-DD+4-PadP$22)") (class "Default")
      (node (ref "U$3") (pin "P$22") (pinfunction "DD+4_P$22") (pintype "bidirectional"))
    )
    (net (code "86") (name "unconnected-(U$3-DD-4-PadP$21)") (class "Default")
      (node (ref "U$3") (pin "P$21") (pinfunction "DD-4_P$21") (pintype "bidirectional"))
    )
    (net (code "87") (name "unconnected-(U$3-GREEN#1-PadP$45)") (class "Default")
      (node (ref "U$3") (pin "P$45") (pinfunction "GREEN#1_P$45") (pintype "bidirectional"))
    )
    (net (code "88") (name "unconnected-(U$3-GREEN#2-PadP$35)") (class "Default")
      (node (ref "U$3") (pin "P$35") (pinfunction "GREEN#2_P$35") (pintype "bidirectional"))
    )
    (net (code "89") (name "unconnected-(U$3-GREEN#3-PadP$32)") (class "Default")
      (node (ref "U$3") (pin "P$32") (pinfunction "GREEN#3_P$32") (pintype "bidirectional"))
    )
    (net (code "90") (name "unconnected-(U$3-GREEN#4-PadP$23)") (class "Default")
      (node (ref "U$3") (pin "P$23") (pinfunction "GREEN#4_P$23") (pintype "bidirectional"))
    )
    (net (code "91") (name "unconnected-(U$3-OVR#1-PadP$42)") (class "Default")
      (node (ref "U$3") (pin "P$42") (pinfunction "OVR#1_P$42") (pintype "bidirectional"))
    )
    (net (code "92") (name "unconnected-(U$3-OVR#2-PadP$40)") (class "Default")
      (node (ref "U$3") (pin "P$40") (pinfunction "OVR#2_P$40") (pintype "bidirectional"))
    )
    (net (code "93") (name "unconnected-(U$3-OVR#3-PadP$30)") (class "Default")
      (node (ref "U$3") (pin "P$30") (pinfunction "OVR#3_P$30") (pintype "bidirectional"))
    )
    (net (code "94") (name "unconnected-(U$3-OVR#4-PadP$28)") (class "Default")
      (node (ref "U$3") (pin "P$28") (pinfunction "OVR#4_P$28") (pintype "bidirectional"))
    )
    (net (code "95") (name "unconnected-(U$3-PWR#1{slash}I2C_SDA-PadP$43)") (class "Default")
      (node (ref "U$3") (pin "P$43") (pinfunction "PWR#1/I2C_SDA_P$43") (pintype "bidirectional"))
    )
    (net (code "96") (name "unconnected-(U$3-PWR#2-PadP$41)") (class "Default")
      (node (ref "U$3") (pin "P$41") (pinfunction "PWR#2_P$41") (pintype "bidirectional"))
    )
    (net (code "97") (name "unconnected-(U$3-PWR#3-PadP$31)") (class "Default")
      (node (ref "U$3") (pin "P$31") (pinfunction "PWR#3_P$31") (pintype "bidirectional"))
    )
    (net (code "98") (name "unconnected-(U$3-PWR#4-PadP$29)") (class "Default")
      (node (ref "U$3") (pin "P$29") (pinfunction "PWR#4_P$29") (pintype "bidirectional"))
    )
    (net (code "99") (name "unconnected-(U$4-Pad3VO)") (class "Default")
      (node (ref "U$4") (pin "3VO") (pinfunction "3VO_3VO") (pintype "bidirectional"))
    )
    (net (code "100") (name "unconnected-(U$4-PadADR)") (class "Default")
      (node (ref "U$4") (pin "ADR") (pinfunction "ADR_ADR") (pintype "bidirectional"))
    )
    (net (code "101") (name "unconnected-(U$4-PadINT)") (class "Default")
      (node (ref "U$4") (pin "INT") (pinfunction "INT_INT") (pintype "bidirectional"))
    )
    (net (code "102") (name "unconnected-(U$4-PadPS0)") (class "Default")
      (node (ref "U$4") (pin "PS0") (pinfunction "PS0_PS0") (pintype "bidirectional"))
    )
    (net (code "103") (name "unconnected-(U$4-PadPS1)") (class "Default")
      (node (ref "U$4") (pin "PS1") (pinfunction "PS1_PS1") (pintype "bidirectional"))
    )
    (net (code "104") (name "unconnected-(U$4-PadRST)") (class "Default")
      (node (ref "U$4") (pin "RST") (pinfunction "RST_RST") (pintype "bidirectional"))
    )
  )
)
